# Sensor_Connection.net
KiCad netlist of a schematic drawn in Altium Designer
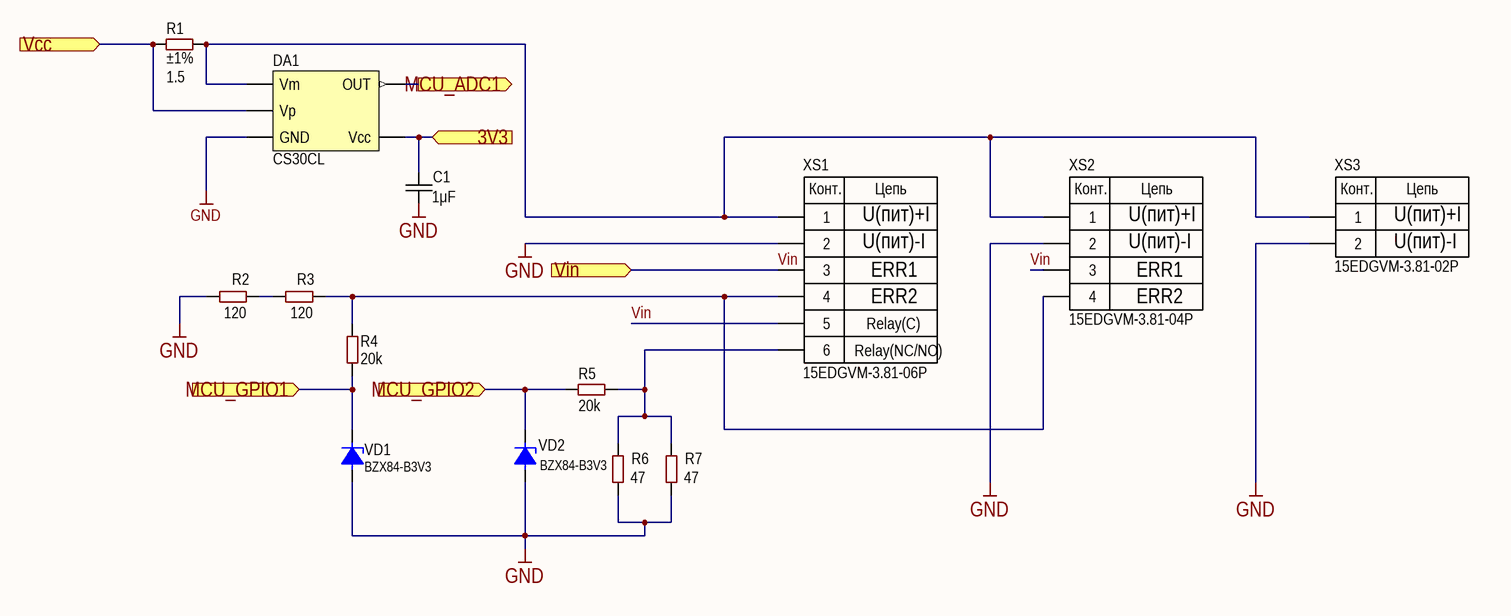
[diagram p0: Sensor Connection.SchDoc]

(export (version "E")
  (design (tool "Eeschema 10.0.6"))
  (components
    (comp (ref "C1")
      (value "1μF")
      (footprint "CAP: 0603")
      (fields
        (field (name "MANUFACTURER") "Yageo")
        (field (name "PARTNUMBER") "CC0603KRX7R7BB104")
        (field (name "VALUEMANUFACTURERPARTNUMBER") "Ceramic capacitor, 1μF, X7R, ±10%, 16V, 0603, -55...+125°C")
      )
      (libsource (lib "capacitor") (part "Ceramic_0603"))
    )
    (comp (ref "DA1")
      (value "CS30CL")
      (footprint "SOT23-5")
      (description "High side current sense high voltage op amp")
      (libsource (lib "ic-sensor") (part "CS30CL"))
    )
    (comp (ref "R1")
      (value "1.5")
      (footprint "RES: 2512")
      (fields
        (field (name "MANUFACTURER") "Yageo")
        (field (name "PARTNUMBER") "RC2512JK-07100RL")
        (field (name "VALUEMANUFACTURERPARTNUMBER") "Resistor film, 1.5, ±1%, 2512, 1W, -55...+125°C")
        (field (name "TOLERANCE") "±1%")
      )
      (libsource (lib "resistor") (part "Resistor_2512"))
    )
    (comp (ref "R2")
      (value "120")
      (footprint "MFR-2W")
      (description "MFR200JT-73- 120R")
      (libsource (lib "resistor") (part "Resistor_DIP_2W"))
    )
    (comp (ref "R3")
      (value "120")
      (footprint "MFR-2W")
      (description "MFR200JT-73- 120R")
      (libsource (lib "resistor") (part "Resistor_DIP_2W"))
    )
    (comp (ref "R4")
      (value "20k")
      (footprint "RES: 0603")
      (fields
        (field (name "MANUFACTURER") "Yageo")
        (field (name "PARTNUMBER") "RC0603JR-07100RL")
        (field (name "VALUEMANUFACTURERPARTNUMBER") "Resistor film, 20k, ±5%, 0603, 0.1W, -55...+125°C")
      )
      (libsource (lib "") (part "Resistor_0603_1"))
    )
    (comp (ref "R5")
      (value "20k")
      (footprint "RES: 0603")
      (fields
        (field (name "MANUFACTURER") "Yageo")
        (field (name "PARTNUMBER") "RC0603JR-07100RL")
        (field (name "VALUEMANUFACTURERPARTNUMBER") "Resistor film, 20k, ±5%, 0603, 0.1W, -55...+125°C")
      )
      (libsource (lib "resistor") (part "Resistor_0603"))
    )
    (comp (ref "R6")
      (value "47")
      (footprint "SQP-10")
      (description "SQP10AJB-47R")
      (libsource (lib "resistor") (part "SQP-10W"))
    )
    (comp (ref "R7")
      (value "47")
      (footprint "SQP-10")
      (description "SQP10AJB-47R")
      (libsource (lib "resistor") (part "SQP-10W"))
    )
    (comp (ref "VD1") (value "BZX84-B3V3") (footprint "SOT23") (libsource (lib "diode") (part "BZX84-B3V3")))
    (comp (ref "VD2") (value "BZX84-B3V3") (footprint "SOT23") (libsource (lib "diode") (part "BZX84-B3V3")))
    (comp (ref "XS1")
      (value "15EDGVM-3.81-06P")
      (footprint "CON: 15EDGVM-3.81-06P")
      (libsource (lib "connector") (part "15EDGVM-3.81-06P"))
    )
    (comp (ref "XS2")
      (value "15EDGVM-3.81-04P")
      (footprint "CON: 15EDGVM-3.81-04P")
      (libsource (lib "connector") (part "15EDGVM-3.81-04P"))
    )
    (comp (ref "XS3")
      (value "15EDGVM-3.81-02P")
      (footprint "CON: 15EDGVM-3.81-02P")
      (libsource (lib "connector") (part "15EDGVM-3.81-02P"))
    )
  )
  (nets
    (net (code "1") (name "/3V3") (class "Default")
      (node (ref "C1") (pin "2") (pinfunction "2_2") (pintype "passive"))
      (node (ref "DA1") (pin "5") (pinfunction "Vcc_5") (pintype "power_in"))
    )
    (net (code "2") (name "/MCU_ADC1") (class "Default")
      (node (ref "DA1") (pin "1") (pinfunction "OUT_1") (pintype "output"))
    )
    (net (code "3") (name "/MCU_GPIO1") (class "Default")
      (node (ref "R4") (pin "1") (pinfunction "1_1") (pintype "passive"))
      (node (ref "VD1") (pin "2") (pinfunction "1_2") (pintype "passive"))
    )
    (net (code "4") (name "/MCU_GPIO2") (class "Default")
      (node (ref "R5") (pin "1") (pinfunction "1_1") (pintype "passive"))
      (node (ref "VD2") (pin "2") (pinfunction "1_2") (pintype "passive"))
    )
    (net (code "5") (name "/Vcc") (class "Default")
      (node (ref "DA1") (pin "3") (pinfunction "Vp_3") (pintype "passive"))
      (node (ref "R1") (pin "1") (pinfunction "1_1") (pintype "passive"))
    )
    (net (code "6") (name "/Vin") (class "Default")
      (node (ref "XS1") (pin "3") (pinfunction "3_3") (pintype "passive"))
      (node (ref "XS1") (pin "5") (pinfunction "5_5") (pintype "passive"))
      (node (ref "XS2") (pin "3") (pinfunction "3_3") (pintype "passive"))
    )
    (net (code "7") (name "GND") (class "Default")
      (node (ref "C1") (pin "1") (pinfunction "1_1") (pintype "passive"))
      (node (ref "DA1") (pin "2") (pinfunction "GND_2") (pintype "power_in"))
      (node (ref "R2") (pin "1") (pinfunction "1_1") (pintype "passive"))
      (node (ref "R6") (pin "1") (pinfunction "1_1") (pintype "passive"))
      (node (ref "R7") (pin "1") (pinfunction "1_1") (pintype "passive"))
      (node (ref "VD1") (pin "1") (pinfunction "2_1") (pintype "passive"))
      (node (ref "VD2") (pin "1") (pinfunction "2_1") (pintype "passive"))
      (node (ref "XS1") (pin "2") (pinfunction "2_2") (pintype "passive"))
      (node (ref "XS2") (pin "2") (pinfunction "2_2") (pintype "passive"))
      (node (ref "XS3") (pin "2") (pinfunction "2_2") (pintype "passive"))
    )
    (net (code "8") (name "Net-(DA1-Vm)") (class "Default")
      (node (ref "DA1") (pin "4") (pinfunction "Vm_4") (pintype "passive"))
      (node (ref "R1") (pin "2") (pinfunction "2_2") (pintype "passive"))
      (node (ref "XS1") (pin "1") (pinfunction "1_1") (pintype "passive"))
      (node (ref "XS2") (pin "1") (pinfunction "1_1") (pintype "passive"))
      (node (ref "XS3") (pin "1") (pinfunction "1_1") (pintype "passive"))
    )
    (net (code "9") (name "Net-(R2-Pad2)") (class "Default")
      (node (ref "R2") (pin "2") (pinfunction "2_2") (pintype "passive"))
      (node (ref "R3") (pin "1") (pinfunction "1_1") (pintype "passive"))
    )
    (net (code "10") (name "Net-(R3-Pad2)") (class "Default")
      (node (ref "R3") (pin "2") (pinfunction "2_2") (pintype "passive"))
      (node (ref "R4") (pin "2") (pinfunction "2_2") (pintype "passive"))
      (node (ref "XS1") (pin "4") (pinfunction "4_4") (pintype "passive"))
      (node (ref "XS2") (pin "4") (pinfunction "4_4") (pintype "passive"))
    )
    (net (code "11") (name "Net-(R5-Pad2)") (class "Default")
      (node (ref "R5") (pin "2") (pinfunction "2_2") (pintype "passive"))
      (node (ref "R6") (pin "2") (pinfunction "2_2") (pintype "passive"))
      (node (ref "R7") (pin "2") (pinfunction "2_2") (pintype "passive"))
      (node (ref "XS1") (pin "6") (pinfunction "6_6") (pintype "passive"))
    )
  )
)
